# Flipper-ESP32-S2.net
KiCad netlist of a schematic drawn in EAGLE
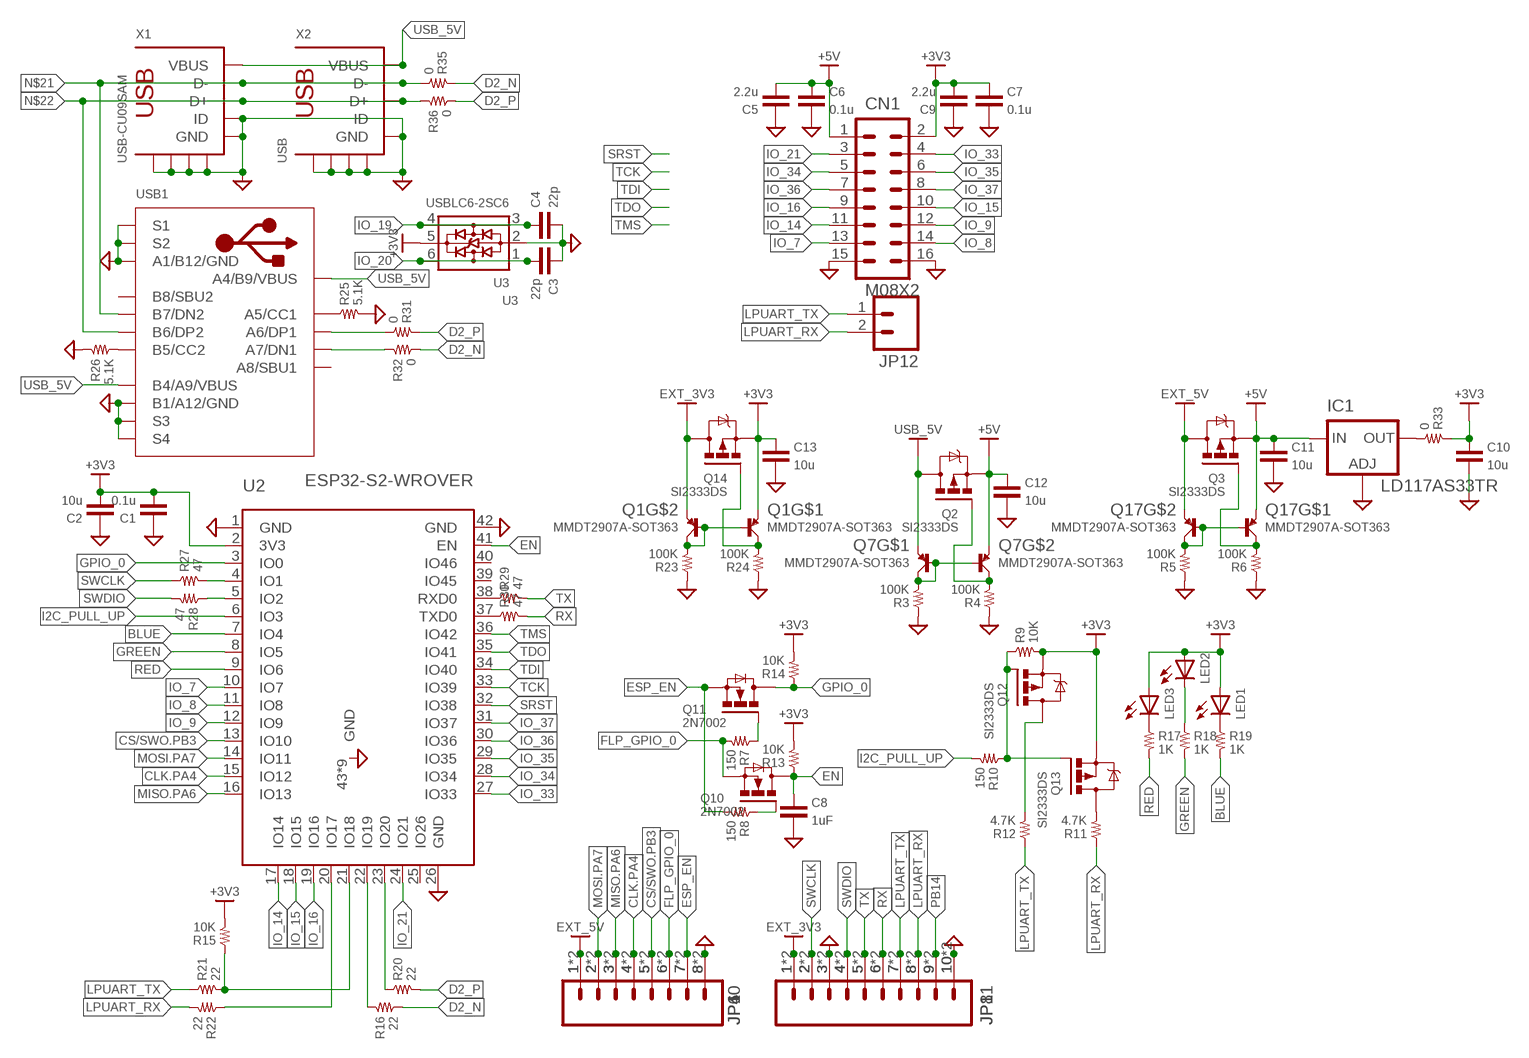
[diagram p0: schematic, sheet 1]

(export (version "E")
  (design (tool "Eeschema 10.0.6"))
  (components
    (comp (ref "C1")
      (value "0.1u")
      (footprint "eagle-import:0603")
      (libsource (lib "eagle-import") (part "CAP-0603"))
    )
    (comp (ref "C2")
      (value "10u")
      (footprint "eagle-import:0805")
      (libsource (lib "eagle-import") (part "CAP-0805"))
    )
    (comp (ref "C3")
      (value "22p")
      (footprint "eagle-import:0603")
      (libsource (lib "eagle-import") (part "CAP-0603"))
    )
    (comp (ref "C4")
      (value "22p")
      (footprint "eagle-import:0603")
      (libsource (lib "eagle-import") (part "CAP-0603"))
    )
    (comp (ref "C5")
      (value "2.2u")
      (footprint "eagle-import:0603")
      (libsource (lib "eagle-import") (part "CAP-0603"))
    )
    (comp (ref "C6")
      (value "0.1u")
      (footprint "eagle-import:0603")
      (libsource (lib "eagle-import") (part "CAP-0603"))
    )
    (comp (ref "C7")
      (value "0.1u")
      (footprint "eagle-import:0603")
      (libsource (lib "eagle-import") (part "CAP-0603"))
    )
    (comp (ref "C8")
      (value "1uF")
      (footprint "eagle-import:0603")
      (libsource (lib "eagle-import") (part "CAP-0603"))
    )
    (comp (ref "C9")
      (value "2.2u")
      (footprint "eagle-import:0603")
      (libsource (lib "eagle-import") (part "CAP-0603"))
    )
    (comp (ref "C10")
      (value "10u")
      (footprint "eagle-import:0805")
      (libsource (lib "eagle-import") (part "CAP-0805"))
    )
    (comp (ref "C11")
      (value "10u")
      (footprint "eagle-import:0805")
      (libsource (lib "eagle-import") (part "CAP-0805"))
    )
    (comp (ref "C12")
      (value "10u")
      (footprint "eagle-import:0805")
      (libsource (lib "eagle-import") (part "CAP-0805"))
    )
    (comp (ref "C13")
      (value "10u")
      (footprint "eagle-import:0805")
      (libsource (lib "eagle-import") (part "CAP-0805"))
    )
    (comp (ref "CN1")
      (value "M08X2")
      (footprint "eagle-import:2X8")
      (libsource (lib "eagle-import") (part "M08X2"))
    )
    (comp (ref "IC1")
      (value "LD117AS33TR")
      (footprint "eagle-import:SOT223")
      (libsource (lib "eagle-import") (part "LD117A?S33TR"))
    )
    (comp (ref "JP1")
      (value "M10\"")
      (footprint "eagle-import:1X10")
      (libsource (lib "eagle-import") (part "M10{dblquote}"))
    )
    (comp (ref "JP4")
      (value "M08SMD-COMBO")
      (footprint "eagle-import:1X08_SMD_COMBINED")
      (libsource (lib "eagle-import") (part "M08SMD-COMBO"))
    )
    (comp (ref "JP6")
      (value "M081X08")
      (footprint "eagle-import:1X08")
      (libsource (lib "eagle-import") (part "M081X08"))
    )
    (comp (ref "JP8")
      (value "M10COMBINED")
      (footprint "eagle-import:1X10_SMD_COMBINED")
      (libsource (lib "eagle-import") (part "M10COMBINED"))
    )
    (comp (ref "JP10")
      (value "M081X08")
      (footprint "eagle-import:1X08")
      (libsource (lib "eagle-import") (part "M081X08"))
    )
    (comp (ref "JP11")
      (value "M10\"")
      (footprint "eagle-import:1X10")
      (libsource (lib "eagle-import") (part "M10{dblquote}"))
    )
    (comp (ref "JP12")
      (value "M02PTH")
      (footprint "eagle-import:1X02")
      (libsource (lib "eagle-import") (part "M02PTH"))
    )
    (comp (ref "LED1")
      (value "LEDCHIPLED_0603")
      (footprint "eagle-import:CHIPLED_0603")
      (libsource (lib "eagle-import") (part "LEDCHIPLED_0603"))
    )
    (comp (ref "LED2")
      (value "LEDCHIPLED_0603")
      (footprint "eagle-import:CHIPLED_0603")
      (libsource (lib "eagle-import") (part "LEDCHIPLED_0603"))
    )
    (comp (ref "LED3")
      (value "LEDCHIPLED_0603")
      (footprint "eagle-import:CHIPLED_0603")
      (libsource (lib "eagle-import") (part "LEDCHIPLED_0603"))
    )
    (comp (ref "Q1")
      (value "MMDT2907A-SOT363")
      (footprint "eagle-import:SOT363")
      (libsource (lib "eagle-import") (part "MMDT2907A-SOT363"))
    )
    (comp (ref "Q2")
      (value "SI2333DS")
      (footprint "eagle-import:SOT-23")
      (libsource (lib "eagle-import") (part "IRLML6401"))
    )
    (comp (ref "Q3")
      (value "SI2333DS")
      (footprint "eagle-import:SOT-23")
      (libsource (lib "eagle-import") (part "IRLML6401"))
    )
    (comp (ref "Q7")
      (value "MMDT2907A-SOT363")
      (footprint "eagle-import:SOT363")
      (libsource (lib "eagle-import") (part "MMDT2907A-SOT363"))
    )
    (comp (ref "Q10")
      (value "2N7002")
      (footprint "eagle-import:SOT-23")
      (libsource (lib "eagle-import") (part "MOSFET-N-SOT23"))
    )
    (comp (ref "Q11")
      (value "2N7002")
      (footprint "eagle-import:SOT-23")
      (libsource (lib "eagle-import") (part "MOSFET-N-SOT23"))
    )
    (comp (ref "Q12")
      (value "SI2333DS")
      (footprint "eagle-import:SOT-23")
      (libsource (lib "eagle-import") (part "IRLML6401"))
    )
    (comp (ref "Q13")
      (value "SI2333DS")
      (footprint "eagle-import:SOT-23")
      (libsource (lib "eagle-import") (part "IRLML6401"))
    )
    (comp (ref "Q14")
      (value "SI2333DS")
      (footprint "eagle-import:SOT-23")
      (libsource (lib "eagle-import") (part "IRLML6401"))
    )
    (comp (ref "Q17")
      (value "MMDT2907A-SOT363")
      (footprint "eagle-import:SOT363")
      (libsource (lib "eagle-import") (part "MMDT2907A-SOT363"))
    )
    (comp (ref "R3")
      (value "100K")
      (footprint "eagle-import:0603")
      (libsource (lib "eagle-import") (part "RESISTOR-0603"))
    )
    (comp (ref "R4")
      (value "100K")
      (footprint "eagle-import:0603")
      (libsource (lib "eagle-import") (part "RESISTOR-0603"))
    )
    (comp (ref "R5")
      (value "100K")
      (footprint "eagle-import:0603")
      (libsource (lib "eagle-import") (part "RESISTOR-0603"))
    )
    (comp (ref "R6")
      (value "100K")
      (footprint "eagle-import:0603")
      (libsource (lib "eagle-import") (part "RESISTOR-0603"))
    )
    (comp (ref "R7")
      (value "150")
      (footprint "eagle-import:0603")
      (libsource (lib "eagle-import") (part "RESISTOR-0603"))
    )
    (comp (ref "R8")
      (value "150")
      (footprint "eagle-import:0603")
      (libsource (lib "eagle-import") (part "RESISTOR-0603"))
    )
    (comp (ref "R9")
      (value "10K")
      (footprint "eagle-import:0603")
      (libsource (lib "eagle-import") (part "RESISTOR-0603"))
    )
    (comp (ref "R10")
      (value "150")
      (footprint "eagle-import:0603")
      (libsource (lib "eagle-import") (part "RESISTOR-0603"))
    )
    (comp (ref "R11")
      (value "4.7K")
      (footprint "eagle-import:0603")
      (libsource (lib "eagle-import") (part "RESISTOR-0603"))
    )
    (comp (ref "R12")
      (value "4.7K")
      (footprint "eagle-import:0603")
      (libsource (lib "eagle-import") (part "RESISTOR-0603"))
    )
    (comp (ref "R13")
      (value "10K")
      (footprint "eagle-import:0603")
      (libsource (lib "eagle-import") (part "RESISTOR-0603"))
    )
    (comp (ref "R14")
      (value "10K")
      (footprint "eagle-import:0603")
      (libsource (lib "eagle-import") (part "RESISTOR-0603"))
    )
    (comp (ref "R15")
      (value "10K")
      (footprint "eagle-import:0603")
      (libsource (lib "eagle-import") (part "RESISTOR-0603"))
    )
    (comp (ref "R16")
      (value "22")
      (footprint "eagle-import:0603")
      (libsource (lib "eagle-import") (part "RESISTOR-0603"))
    )
    (comp (ref "R17")
      (value "1K")
      (footprint "eagle-import:0603")
      (libsource (lib "eagle-import") (part "RESISTOR-0603"))
    )
    (comp (ref "R18")
      (value "1K")
      (footprint "eagle-import:0603")
      (libsource (lib "eagle-import") (part "RESISTOR-0603"))
    )
    (comp (ref "R19")
      (value "1K")
      (footprint "eagle-import:0603")
      (libsource (lib "eagle-import") (part "RESISTOR-0603"))
    )
    (comp (ref "R20")
      (value "22")
      (footprint "eagle-import:0603")
      (libsource (lib "eagle-import") (part "RESISTOR-0603"))
    )
    (comp (ref "R21")
      (value "22")
      (footprint "eagle-import:0603")
      (libsource (lib "eagle-import") (part "RESISTOR-0603"))
    )
    (comp (ref "R22")
      (value "22")
      (footprint "eagle-import:0603")
      (libsource (lib "eagle-import") (part "RESISTOR-0603"))
    )
    (comp (ref "R23")
      (value "100K")
      (footprint "eagle-import:0603")
      (libsource (lib "eagle-import") (part "RESISTOR-0603"))
    )
    (comp (ref "R24")
      (value "100K")
      (footprint "eagle-import:0603")
      (libsource (lib "eagle-import") (part "RESISTOR-0603"))
    )
    (comp (ref "R25")
      (value "5.1K")
      (footprint "eagle-import:0603")
      (libsource (lib "eagle-import") (part "RESISTOR-0603"))
    )
    (comp (ref "R26")
      (value "5.1K")
      (footprint "eagle-import:0603")
      (libsource (lib "eagle-import") (part "RESISTOR-0603"))
    )
    (comp (ref "R27")
      (value "47")
      (footprint "eagle-import:0603")
      (libsource (lib "eagle-import") (part "RESISTOR-0603"))
    )
    (comp (ref "R28")
      (value "47")
      (footprint "eagle-import:0603")
      (libsource (lib "eagle-import") (part "RESISTOR-0603"))
    )
    (comp (ref "R29")
      (value "47")
      (footprint "eagle-import:0603")
      (libsource (lib "eagle-import") (part "RESISTOR-0603"))
    )
    (comp (ref "R30")
      (value "47")
      (footprint "eagle-import:0603")
      (libsource (lib "eagle-import") (part "RESISTOR-0603"))
    )
    (comp (ref "R31")
      (value "0")
      (footprint "eagle-import:0402")
      (libsource (lib "eagle-import") (part "RESISTOR-0402"))
    )
    (comp (ref "R32")
      (value "0")
      (footprint "eagle-import:0402")
      (libsource (lib "eagle-import") (part "RESISTOR-0402"))
    )
    (comp (ref "R33")
      (value "0")
      (footprint "eagle-import:0402")
      (libsource (lib "eagle-import") (part "RESISTOR-0402"))
    )
    (comp (ref "R35")
      (value "0")
      (footprint "eagle-import:0402")
      (libsource (lib "eagle-import") (part "RESISTOR-0402"))
    )
    (comp (ref "R36")
      (value "0")
      (footprint "eagle-import:0402")
      (libsource (lib "eagle-import") (part "RESISTOR-0402"))
    )
    (comp (ref "U2")
      (value "ESP32-S2-WROVER")
      (footprint "eagle-import:ESP32-S2-WROVER")
      (libsource (lib "eagle-import") (part "ESP32-S2-WROVER"))
    )
    (comp (ref "U3")
      (value "USBLC6-2SC6")
      (footprint "eagle-import:SOT23-6")
      (libsource (lib "eagle-import") (part "USBLC6-2SC6"))
    )
    (comp (ref "USB1")
      (value "USB2.0-TYPE-C")
      (footprint "eagle-import:USB2.0-TYPE-C")
      (libsource (lib "eagle-import") (part "USB2.0-TYPE-C"))
    )
    (comp (ref "X1")
      (value "USB-CU09SAM")
      (footprint "eagle-import:CU09SAM")
      (libsource (lib "eagle-import") (part "USB-CU09SAM"))
    )
    (comp (ref "X2")
      (value "USB")
      (footprint "eagle-import:473460001")
      (libsource (lib "eagle-import") (part "USB"))
    )
  )
  (nets
    (net (code "1") (name "+3V3") (class "Default")
      (node (ref "C1") (pin "1") (pinfunction "1_1") (pintype "passive"))
      (node (ref "C10") (pin "2") (pinfunction "2_2") (pintype "passive"))
      (node (ref "C13") (pin "2") (pinfunction "2_2") (pintype "passive"))
      (node (ref "C2") (pin "1") (pinfunction "1_1") (pintype "passive"))
      (node (ref "C7") (pin "2") (pinfunction "2_2") (pintype "passive"))
      (node (ref "C9") (pin "1") (pinfunction "1_1") (pintype "passive"))
      (node (ref "CN1") (pin "2") (pinfunction "2_2") (pintype "passive"))
      (node (ref "LED1") (pin "A") (pinfunction "A_A") (pintype "passive"))
      (node (ref "LED2") (pin "A") (pinfunction "A_A") (pintype "passive"))
      (node (ref "LED3") (pin "A") (pinfunction "A_A") (pintype "passive"))
      (node (ref "Q1") (pin "1") (pinfunction "E_1") (pintype "passive"))
      (node (ref "Q12") (pin "2") (pinfunction "S_2") (pintype "passive"))
      (node (ref "Q13") (pin "2") (pinfunction "S_2") (pintype "passive"))
      (node (ref "Q14") (pin "2") (pinfunction "S_2") (pintype "passive"))
      (node (ref "R13") (pin "2") (pinfunction "2_2") (pintype "passive"))
      (node (ref "R14") (pin "2") (pinfunction "2_2") (pintype "passive"))
      (node (ref "R15") (pin "2") (pinfunction "2_2") (pintype "passive"))
      (node (ref "R33") (pin "1") (pinfunction "1_1") (pintype "passive"))
      (node (ref "R9") (pin "2") (pinfunction "2_2") (pintype "passive"))
      (node (ref "U2") (pin "2") (pinfunction "3V3_2") (pintype "power_in"))
      (node (ref "U3") (pin "5") (pinfunction "VBUS_5") (pintype "passive"))
    )
    (net (code "2") (name "+5V") (class "Default")
      (node (ref "C11") (pin "2") (pinfunction "2_2") (pintype "passive"))
      (node (ref "C12") (pin "2") (pinfunction "2_2") (pintype "passive"))
      (node (ref "C5") (pin "1") (pinfunction "1_1") (pintype "passive"))
      (node (ref "C6") (pin "2") (pinfunction "2_2") (pintype "passive"))
      (node (ref "CN1") (pin "1") (pinfunction "1_1") (pintype "passive"))
      (node (ref "IC1") (pin "3") (pinfunction "IN_3") (pintype "input"))
      (node (ref "Q17") (pin "1") (pinfunction "E_1") (pintype "passive"))
      (node (ref "Q2") (pin "2") (pinfunction "S_2") (pintype "passive"))
      (node (ref "Q3") (pin "2") (pinfunction "S_2") (pintype "passive"))
      (node (ref "Q7") (pin "4") (pinfunction "E_4") (pintype "passive"))
    )
    (net (code "3") (name "BLUE") (class "Default")
      (node (ref "R19") (pin "2") (pinfunction "2_2") (pintype "passive"))
      (node (ref "U2") (pin "7") (pinfunction "IO4_7") (pintype "bidirectional"))
    )
    (net (code "4") (name "CLK.PA4") (class "Default")
      (node (ref "JP10") (pin "4") (pinfunction "4_4") (pintype "passive"))
      (node (ref "JP4") (pin "4") (pinfunction "4_4") (pintype "passive"))
      (node (ref "JP4") (pin "4@2") (pinfunction "4_4@2") (pintype "passive"))
      (node (ref "JP6") (pin "4") (pinfunction "4_4") (pintype "passive"))
      (node (ref "U2") (pin "15") (pinfunction "IO12_15") (pintype "bidirectional"))
    )
    (net (code "5") (name "CS{slash}SWO.PB3") (class "Default")
      (node (ref "JP10") (pin "5") (pinfunction "5_5") (pintype "passive"))
      (node (ref "JP4") (pin "5") (pinfunction "5_5") (pintype "passive"))
      (node (ref "JP4") (pin "5@2") (pinfunction "5_5@2") (pintype "passive"))
      (node (ref "JP6") (pin "5") (pinfunction "5_5") (pintype "passive"))
      (node (ref "U2") (pin "13") (pinfunction "IO10_13") (pintype "bidirectional"))
    )
    (net (code "6") (name "D2_N") (class "Default")
      (node (ref "R16") (pin "2") (pinfunction "2_2") (pintype "passive"))
      (node (ref "R32") (pin "2") (pinfunction "2_2") (pintype "passive"))
      (node (ref "R35") (pin "1") (pinfunction "1_1") (pintype "passive"))
    )
    (net (code "7") (name "D2_P") (class "Default")
      (node (ref "R20") (pin "2") (pinfunction "2_2") (pintype "passive"))
      (node (ref "R31") (pin "1") (pinfunction "1_1") (pintype "passive"))
      (node (ref "R36") (pin "2") (pinfunction "2_2") (pintype "passive"))
    )
    (net (code "8") (name "EN") (class "Default")
      (node (ref "C8") (pin "2") (pinfunction "2_2") (pintype "passive"))
      (node (ref "Q10") (pin "3") (pinfunction "D_3") (pintype "passive"))
      (node (ref "R13") (pin "1") (pinfunction "1_1") (pintype "passive"))
      (node (ref "U2") (pin "41") (pinfunction "EN_41") (pintype "bidirectional"))
    )
    (net (code "9") (name "ESP_EN") (class "Default")
      (node (ref "JP10") (pin "7") (pinfunction "7_7") (pintype "passive"))
      (node (ref "JP4") (pin "7") (pinfunction "7_7") (pintype "passive"))
      (node (ref "JP4") (pin "7@2") (pinfunction "7_7@2") (pintype "passive"))
      (node (ref "JP6") (pin "7") (pinfunction "7_7") (pintype "passive"))
      (node (ref "Q11") (pin "2") (pinfunction "S_2") (pintype "passive"))
      (node (ref "R8") (pin "2") (pinfunction "2_2") (pintype "passive"))
    )
    (net (code "10") (name "EXT_3V3") (class "Default")
      (node (ref "JP1") (pin "1") (pinfunction "1_1") (pintype "passive"))
      (node (ref "JP11") (pin "1") (pinfunction "1_1") (pintype "passive"))
      (node (ref "JP8") (pin "1") (pinfunction "1_1") (pintype "passive"))
      (node (ref "JP8") (pin "1@2") (pinfunction "1_1@2") (pintype "passive"))
      (node (ref "Q1") (pin "4") (pinfunction "E_4") (pintype "passive"))
      (node (ref "Q14") (pin "3") (pinfunction "D_3") (pintype "passive"))
    )
    (net (code "11") (name "EXT_5V") (class "Default")
      (node (ref "JP10") (pin "1") (pinfunction "1_1") (pintype "passive"))
      (node (ref "JP4") (pin "1") (pinfunction "1_1") (pintype "passive"))
      (node (ref "JP4") (pin "1@2") (pinfunction "1_1@2") (pintype "passive"))
      (node (ref "JP6") (pin "1") (pinfunction "1_1") (pintype "passive"))
      (node (ref "Q17") (pin "4") (pinfunction "E_4") (pintype "passive"))
      (node (ref "Q3") (pin "3") (pinfunction "D_3") (pintype "passive"))
    )
    (net (code "12") (name "FLP_GPIO_0") (class "Default")
      (node (ref "JP10") (pin "6") (pinfunction "6_6") (pintype "passive"))
      (node (ref "JP4") (pin "6") (pinfunction "6_6") (pintype "passive"))
      (node (ref "JP4") (pin "6@2") (pinfunction "6_6@2") (pintype "passive"))
      (node (ref "JP6") (pin "6") (pinfunction "6_6") (pintype "passive"))
      (node (ref "Q10") (pin "2") (pinfunction "S_2") (pintype "passive"))
      (node (ref "R7") (pin "2") (pinfunction "2_2") (pintype "passive"))
    )
    (net (code "13") (name "GND") (class "Default")
      (node (ref "C1") (pin "2") (pinfunction "2_2") (pintype "passive"))
      (node (ref "C10") (pin "1") (pinfunction "1_1") (pintype "passive"))
      (node (ref "C11") (pin "1") (pinfunction "1_1") (pintype "passive"))
      (node (ref "C12") (pin "1") (pinfunction "1_1") (pintype "passive"))
      (node (ref "C13") (pin "1") (pinfunction "1_1") (pintype "passive"))
      (node (ref "C2") (pin "2") (pinfunction "2_2") (pintype "passive"))
      (node (ref "C3") (pin "2") (pinfunction "2_2") (pintype "passive"))
      (node (ref "C4") (pin "1") (pinfunction "1_1") (pintype "passive"))
      (node (ref "C5") (pin "2") (pinfunction "2_2") (pintype "passive"))
      (node (ref "C6") (pin "1") (pinfunction "1_1") (pintype "passive"))
      (node (ref "C7") (pin "1") (pinfunction "1_1") (pintype "passive"))
      (node (ref "C8") (pin "1") (pinfunction "1_1") (pintype "passive"))
      (node (ref "C9") (pin "2") (pinfunction "2_2") (pintype "passive"))
      (node (ref "CN1") (pin "15") (pinfunction "15_15") (pintype "passive"))
      (node (ref "CN1") (pin "16") (pinfunction "16_16") (pintype "passive"))
      (node (ref "IC1") (pin "1") (pinfunction "ADJ_1") (pintype "input"))
      (node (ref "JP1") (pin "10") (pinfunction "10_10") (pintype "passive"))
      (node (ref "JP1") (pin "3") (pinfunction "3_3") (pintype "passive"))
      (node (ref "JP10") (pin "8") (pinfunction "8_8") (pintype "passive"))
      (node (ref "JP11") (pin "10") (pinfunction "10_10") (pintype "passive"))
      (node (ref "JP11") (pin "3") (pinfunction "3_3") (pintype "passive"))
      (node (ref "JP4") (pin "8") (pinfunction "8_8") (pintype "passive"))
      (node (ref "JP4") (pin "8@2") (pinfunction "8_8@2") (pintype "passive"))
      (node (ref "JP6") (pin "8") (pinfunction "8_8") (pintype "passive"))
      (node (ref "JP8") (pin "10") (pinfunction "10_10") (pintype "passive"))
      (node (ref "JP8") (pin "10@2") (pinfunction "10_10@2") (pintype "passive"))
      (node (ref "JP8") (pin "3") (pinfunction "3_3") (pintype "passive"))
      (node (ref "JP8") (pin "3@2") (pinfunction "3_3@2") (pintype "passive"))
      (node (ref "R23") (pin "1") (pinfunction "1_1") (pintype "passive"))
      (node (ref "R24") (pin "1") (pinfunction "1_1") (pintype "passive"))
      (node (ref "R25") (pin "2") (pinfunction "2_2") (pintype "passive"))
      (node (ref "R26") (pin "1") (pinfunction "1_1") (pintype "passive"))
      (node (ref "R3") (pin "1") (pinfunction "1_1") (pintype "passive"))
      (node (ref "R4") (pin "1") (pinfunction "1_1") (pintype "passive"))
      (node (ref "R5") (pin "1") (pinfunction "1_1") (pintype "passive"))
      (node (ref "R6") (pin "1") (pinfunction "1_1") (pintype "passive"))
      (node (ref "U2") (pin "1") (pinfunction "GND_1") (pintype "power_in"))
      (node (ref "U2") (pin "26") (pinfunction "GND_26") (pintype "power_in"))
      (node (ref "U2") (pin "42") (pinfunction "GND_42") (pintype "power_in"))
      (node (ref "U2") (pin "43") (pinfunction "GND_43") (pintype "power_in"))
      (node (ref "U2") (pin "44") (pinfunction "GND_44") (pintype "power_in"))
      (node (ref "U2") (pin "45") (pinfunction "GND_45") (pintype "power_in"))
      (node (ref "U2") (pin "46") (pinfunction "GND_46") (pintype "power_in"))
      (node (ref "U2") (pin "47") (pinfunction "GND_47") (pintype "power_in"))
      (node (ref "U2") (pin "48") (pinfunction "GND_48") (pintype "power_in"))
      (node (ref "U2") (pin "49") (pinfunction "GND_49") (pintype "power_in"))
      (node (ref "U2") (pin "50") (pinfunction "GND_50") (pintype "power_in"))
      (node (ref "U2") (pin "51") (pinfunction "GND_51") (pintype "power_in"))
      (node (ref "U3") (pin "2") (pinfunction "GND_2") (pintype "passive"))
      (node (ref "USB1") (pin "A1_B12") (pinfunction "A1/B12/GND_A1_B12") (pintype "passive"))
      (node (ref "USB1") (pin "B1_A12") (pinfunction "B1/A12/GND_B1_A12") (pintype "passive"))
      (node (ref "USB1") (pin "S1") (pinfunction "S1_S1") (pintype "passive"))
      (node (ref "USB1") (pin "S2") (pinfunction "S2_S2") (pintype "passive"))
      (node (ref "USB1") (pin "S3") (pinfunction "S3_S3") (pintype "passive"))
      (node (ref "USB1") (pin "S4") (pinfunction "S4_S4") (pintype "passive"))
      (node (ref "USB1") (pin "S5") (pinfunction "S1_S5") (pintype "passive"))
      (node (ref "USB1") (pin "S6") (pinfunction "S2_S6") (pintype "passive"))
      (node (ref "X1") (pin "4") (pinfunction "ID_4") (pintype "bidirectional"))
      (node (ref "X1") (pin "5") (pinfunction "GND_5") (pintype "power_in"))
      (node (ref "X1") (pin "GND@1") (pinfunction "GND_GND@1") (pintype "power_in"))
      (node (ref "X1") (pin "GND@2") (pinfunction "GND_GND@2") (pintype "power_in"))
      (node (ref "X1") (pin "GND@3") (pinfunction "GND_GND@3") (pintype "power_in"))
      (node (ref "X1") (pin "GND@4") (pinfunction "GND_GND@4") (pintype "power_in"))
      (node (ref "X2") (pin "4") (pinfunction "ID_4") (pintype "bidirectional"))
      (node (ref "X2") (pin "5") (pinfunction "GND_5") (pintype "power_in"))
      (node (ref "X2") (pin "EP@1") (pinfunction "GND_EP@1") (pintype "power_in"))
      (node (ref "X2") (pin "EP@2") (pinfunction "GND_EP@2") (pintype "power_in"))
      (node (ref "X2") (pin "EP@3") (pinfunction "GND_EP@3") (pintype "power_in"))
      (node (ref "X2") (pin "EP@4") (pinfunction "GND_EP@4") (pintype "power_in"))
    )
    (net (code "14") (name "GPIO_0") (class "Default")
      (node (ref "Q11") (pin "3") (pinfunction "D_3") (pintype "passive"))
      (node (ref "R14") (pin "1") (pinfunction "1_1") (pintype "passive"))
      (node (ref "U2") (pin "3") (pinfunction "IO0_3") (pintype "bidirectional"))
    )
    (net (code "15") (name "GREEN") (class "Default")
      (node (ref "R18") (pin "2") (pinfunction "2_2") (pintype "passive"))
      (node (ref "U2") (pin "8") (pinfunction "IO5_8") (pintype "bidirectional"))
    )
    (net (code "16") (name "I2C_PULL_UP") (class "Default")
      (node (ref "R10") (pin "2") (pinfunction "2_2") (pintype "passive"))
      (node (ref "U2") (pin "6") (pinfunction "IO3_6") (pintype "bidirectional"))
    )
    (net (code "17") (name "IO_7") (class "Default")
      (node (ref "CN1") (pin "13") (pinfunction "13_13") (pintype "passive"))
      (node (ref "U2") (pin "10") (pinfunction "IO7_10") (pintype "bidirectional"))
    )
    (net (code "18") (name "IO_8") (class "Default")
      (node (ref "CN1") (pin "14") (pinfunction "14_14") (pintype "passive"))
      (node (ref "U2") (pin "11") (pinfunction "IO8_11") (pintype "bidirectional"))
    )
    (net (code "19") (name "IO_9") (class "Default")
      (node (ref "CN1") (pin "12") (pinfunction "12_12") (pintype "passive"))
      (node (ref "U2") (pin "12") (pinfunction "IO9_12") (pintype "bidirectional"))
    )
    (net (code "20") (name "IO_14") (class "Default")
      (node (ref "CN1") (pin "11") (pinfunction "11_11") (pintype "passive"))
      (node (ref "U2") (pin "17") (pinfunction "IO14_17") (pintype "bidirectional"))
    )
    (net (code "21") (name "IO_15") (class "Default")
      (node (ref "CN1") (pin "10") (pinfunction "10_10") (pintype "passive"))
      (node (ref "U2") (pin "18") (pinfunction "IO15_18") (pintype "bidirectional"))
    )
    (net (code "22") (name "IO_16") (class "Default")
      (node (ref "CN1") (pin "9") (pinfunction "9_9") (pintype "passive"))
      (node (ref "U2") (pin "19") (pinfunction "IO16_19") (pintype "bidirectional"))
    )
    (net (code "23") (name "IO_19") (class "Default")
      (node (ref "C4") (pin "2") (pinfunction "2_2") (pintype "passive"))
      (node (ref "R16") (pin "1") (pinfunction "1_1") (pintype "passive"))
      (node (ref "U2") (pin "22") (pinfunction "IO19_22") (pintype "bidirectional"))
      (node (ref "U3") (pin "3") (pinfunction "IO2_3") (pintype "passive"))
      (node (ref "U3") (pin "4") (pinfunction "IO2_4") (pintype "passive"))
    )
    (net (code "24") (name "IO_20") (class "Default")
      (node (ref "C3") (pin "1") (pinfunction "1_1") (pintype "passive"))
      (node (ref "R20") (pin "1") (pinfunction "1_1") (pintype "passive"))
      (node (ref "U2") (pin "23") (pinfunction "IO20_23") (pintype "bidirectional"))
      (node (ref "U3") (pin "1") (pinfunction "IO1_1") (pintype "passive"))
      (node (ref "U3") (pin "6") (pinfunction "IO1_6") (pintype "passive"))
    )
    (net (code "25") (name "IO_21") (class "Default")
      (node (ref "CN1") (pin "3") (pinfunction "3_3") (pintype "passive"))
      (node (ref "U2") (pin "24") (pinfunction "IO21_24") (pintype "bidirectional"))
    )
    (net (code "26") (name "IO_33") (class "Default")
      (node (ref "CN1") (pin "4") (pinfunction "4_4") (pintype "passive"))
      (node (ref "U2") (pin "27") (pinfunction "IO33_27") (pintype "bidirectional"))
    )
    (net (code "27") (name "IO_34") (class "Default")
      (node (ref "CN1") (pin "5") (pinfunction "5_5") (pintype "passive"))
      (node (ref "U2") (pin "28") (pinfunction "IO34_28") (pintype "bidirectional"))
    )
    (net (code "28") (name "IO_35") (class "Default")
      (node (ref "CN1") (pin "6") (pinfunction "6_6") (pintype "passive"))
      (node (ref "U2") (pin "29") (pinfunction "IO35_29") (pintype "bidirectional"))
    )
    (net (code "29") (name "IO_36") (class "Default")
      (node (ref "CN1") (pin "7") (pinfunction "7_7") (pintype "passive"))
      (node (ref "U2") (pin "30") (pinfunction "IO36_30") (pintype "bidirectional"))
    )
    (net (code "30") (name "IO_37") (class "Default")
      (node (ref "CN1") (pin "8") (pinfunction "8_8") (pintype "passive"))
      (node (ref "U2") (pin "31") (pinfunction "IO37_31") (pintype "bidirectional"))
    )
    (net (code "31") (name "LPUART_RX") (class "Default")
      (node (ref "JP1") (pin "8") (pinfunction "8_8") (pintype "passive"))
      (node (ref "JP11") (pin "8") (pinfunction "8_8") (pintype "passive"))
      (node (ref "JP12") (pin "2") (pinfunction "2_2") (pintype "passive"))
      (node (ref "JP8") (pin "8") (pinfunction "8_8") (pintype "passive"))
      (node (ref "JP8") (pin "8@2") (pinfunction "8_8@2") (pintype "passive"))
      (node (ref "R11") (pin "1") (pinfunction "1_1") (pintype "passive"))
      (node (ref "R22") (pin "2") (pinfunction "2_2") (pintype "passive"))
    )
    (net (code "32") (name "LPUART_TX") (class "Default")
      (node (ref "JP1") (pin "7") (pinfunction "7_7") (pintype "passive"))
      (node (ref "JP11") (pin "7") (pinfunction "7_7") (pintype "passive"))
      (node (ref "JP12") (pin "1") (pinfunction "1_1") (pintype "passive"))
      (node (ref "JP8") (pin "7") (pinfunction "7_7") (pintype "passive"))
      (node (ref "JP8") (pin "7@2") (pinfunction "7_7@2") (pintype "passive"))
      (node (ref "R12") (pin "1") (pinfunction "1_1") (pintype "passive"))
      (node (ref "R21") (pin "1") (pinfunction "1_1") (pintype "passive"))
    )
    (net (code "33") (name "MISO.PA6") (class "Default")
      (node (ref "JP10") (pin "3") (pinfunction "3_3") (pintype "passive"))
      (node (ref "JP4") (pin "3") (pinfunction "3_3") (pintype "passive"))
      (node (ref "JP4") (pin "3@2") (pinfunction "3_3@2") (pintype "passive"))
      (node (ref "JP6") (pin "3") (pinfunction "3_3") (pintype "passive"))
      (node (ref "U2") (pin "16") (pinfunction "IO13_16") (pintype "bidirectional"))
    )
    (net (code "34") (name "MOSI.PA7") (class "Default")
      (node (ref "JP10") (pin "2") (pinfunction "2_2") (pintype "passive"))
      (node (ref "JP4") (pin "2") (pinfunction "2_2") (pintype "passive"))
      (node (ref "JP4") (pin "2@2") (pinfunction "2_2@2") (pintype "passive"))
      (node (ref "JP6") (pin "2") (pinfunction "2_2") (pintype "passive"))
      (node (ref "U2") (pin "14") (pinfunction "IO11_14") (pintype "bidirectional"))
    )
    (net (code "35") (name "N$21") (class "Default")
      (node (ref "R35") (pin "2") (pinfunction "2_2") (pintype "passive"))
      (node (ref "USB1") (pin "B7") (pinfunction "B7/DN2_B7") (pintype "passive"))
      (node (ref "X1") (pin "2") (pinfunction "D-_2") (pintype "bidirectional"))
      (node (ref "X2") (pin "2") (pinfunction "D-_2") (pintype "bidirectional"))
    )
    (net (code "36") (name "N$22") (class "Default")
      (node (ref "R36") (pin "1") (pinfunction "1_1") (pintype "passive"))
      (node (ref "USB1") (pin "B6") (pinfunction "B6/DP2_B6") (pintype "passive"))
      (node (ref "X1") (pin "3") (pinfunction "D+_3") (pintype "bidirectional"))
      (node (ref "X2") (pin "3") (pinfunction "D+_3") (pintype "bidirectional"))
    )
    (net (code "37") (name "Net-(IC1-OUT-Pad2)") (class "Default")
      (node (ref "IC1") (pin "2") (pinfunction "OUT_2") (pintype "passive"))
      (node (ref "IC1") (pin "4") (pinfunction "OUT_4") (pintype "passive"))
      (node (ref "R33") (pin "2") (pinfunction "2_2") (pintype "passive"))
    )
    (net (code "38") (name "Net-(LED1-PadC)") (class "Default")
      (node (ref "LED1") (pin "C") (pinfunction "C_C") (pintype "passive"))
      (node (ref "R19") (pin "1") (pinfunction "1_1") (pintype "passive"))
    )
    (net (code "39") (name "Net-(LED2-PadC)") (class "Default")
      (node (ref "LED2") (pin "C") (pinfunction "C_C") (pintype "passive"))
      (node (ref "R18") (pin "1") (pinfunction "1_1") (pintype "passive"))
    )
    (net (code "40") (name "Net-(LED3-PadC)") (class "Default")
      (node (ref "LED3") (pin "C") (pinfunction "C_C") (pintype "passive"))
      (node (ref "R17") (pin "1") (pinfunction "1_1") (pintype "passive"))
    )
    (net (code "41") (name "Net-(Q1A-B)") (class "Default")
      (node (ref "Q1") (pin "2") (pinfunction "B_2") (pintype "passive"))
      (node (ref "Q1") (pin "3") (pinfunction "C_3") (pintype "passive"))
      (node (ref "Q1") (pin "5") (pinfunction "B_5") (pintype "passive"))
      (node (ref "R23") (pin "2") (pinfunction "2_2") (pintype "passive"))
    )
    (net (code "42") (name "Net-(Q2-G)") (class "Default")
      (node (ref "Q2") (pin "1") (pinfunction "G_1") (pintype "passive"))
      (node (ref "Q7") (pin "3") (pinfunction "C_3") (pintype "passive"))
      (node (ref "R4") (pin "2") (pinfunction "2_2") (pintype "passive"))
    )
    (net (code "43") (name "Net-(Q7A-B)") (class "Default")
      (node (ref "Q7") (pin "2") (pinfunction "B_2") (pintype "passive"))
      (node (ref "Q7") (pin "5") (pinfunction "B_5") (pintype "passive"))
      (node (ref "Q7") (pin "6") (pinfunction "C_6") (pintype "passive"))
      (node (ref "R3") (pin "2") (pinfunction "2_2") (pintype "passive"))
    )
    (net (code "44") (name "Net-(Q10-G)") (class "Default")
      (node (ref "Q10") (pin "1") (pinfunction "G_1") (pintype "passive"))
      (node (ref "R8") (pin "1") (pinfunction "1_1") (pintype "passive"))
    )
    (net (code "45") (name "Net-(Q11-G)") (class "Default")
      (node (ref "Q11") (pin "1") (pinfunction "G_1") (pintype "passive"))
      (node (ref "R7") (pin "1") (pinfunction "1_1") (pintype "passive"))
    )
    (net (code "46") (name "Net-(Q12-D)") (class "Default")
      (node (ref "Q12") (pin "3") (pinfunction "D_3") (pintype "passive"))
      (node (ref "R12") (pin "2") (pinfunction "2_2") (pintype "passive"))
    )
    (net (code "47") (name "Net-(Q12-G)") (class "Default")
      (node (ref "Q12") (pin "1") (pinfunction "G_1") (pintype "passive"))
      (node (ref "Q13") (pin "1") (pinfunction "G_1") (pintype "passive"))
      (node (ref "R10") (pin "1") (pinfunction "1_1") (pintype "passive"))
      (node (ref "R9") (pin "1") (pinfunction "1_1") (pintype "passive"))
    )
    (net (code "48") (name "Net-(Q13-D)") (class "Default")
      (node (ref "Q13") (pin "3") (pinfunction "D_3") (pintype "passive"))
      (node (ref "R11") (pin "2") (pinfunction "2_2") (pintype "passive"))
    )
    (net (code "49") (name "Net-(Q14-G)") (class "Default")
      (node (ref "Q1") (pin "6") (pinfunction "C_6") (pintype "passive"))
      (node (ref "Q14") (pin "1") (pinfunction "G_1") (pintype "passive"))
      (node (ref "R24") (pin "2") (pinfunction "2_2") (pintype "passive"))
    )
    (net (code "50") (name "Net-(Q17A-B)") (class "Default")
      (node (ref "Q17") (pin "2") (pinfunction "B_2") (pintype "passive"))
      (node (ref "Q17") (pin "3") (pinfunction "C_3") (pintype "passive"))
      (node (ref "Q17") (pin "5") (pinfunction "B_5") (pintype "passive"))
      (node (ref "R5") (pin "2") (pinfunction "2_2") (pintype "passive"))
    )
    (net (code "51") (name "Net-(Q17A-C)") (class "Default")
      (node (ref "Q17") (pin "6") (pinfunction "C_6") (pintype "passive"))
      (node (ref "Q3") (pin "1") (pinfunction "G_1") (pintype "passive"))
      (node (ref "R6") (pin "2") (pinfunction "2_2") (pintype "passive"))
    )
    (net (code "52") (name "Net-(U2-IO1)") (class "Default")
      (node (ref "R27") (pin "2") (pinfunction "2_2") (pintype "passive"))
      (node (ref "U2") (pin "4") (pinfunction "IO1_4") (pintype "bidirectional"))
    )
    (net (code "53") (name "Net-(U2-IO2)") (class "Default")
      (node (ref "R28") (pin "1") (pinfunction "1_1") (pintype "passive"))
      (node (ref "U2") (pin "5") (pinfunction "IO2_5") (pintype "bidirectional"))
    )
    (net (code "54") (name "Net-(U2-IO17)") (class "Default")
      (node (ref "R22") (pin "1") (pinfunction "1_1") (pintype "passive"))
      (node (ref "U2") (pin "20") (pinfunction "IO17_20") (pintype "bidirectional"))
    )
    (net (code "55") (name "Net-(U2-IO18)") (class "Default")
      (node (ref "R15") (pin "1") (pinfunction "1_1") (pintype "passive"))
      (node (ref "R21") (pin "2") (pinfunction "2_2") (pintype "passive"))
      (node (ref "U2") (pin "21") (pinfunction "IO18_21") (pintype "bidirectional"))
    )
    (net (code "56") (name "Net-(U2-RXD0)") (class "Default")
      (node (ref "R29") (pin "1") (pinfunction "1_1") (pintype "passive"))
      (node (ref "U2") (pin "38") (pinfunction "RXD0_38") (pintype "bidirectional"))
    )
    (net (code "57") (name "Net-(U2-TXD0)") (class "Default")
      (node (ref "R30") (pin "1") (pinfunction "1_1") (pintype "passive"))
      (node (ref "U2") (pin "37") (pinfunction "TXD0_37") (pintype "bidirectional"))
    )
    (net (code "58") (name "Net-(USB1-A5{slash}CC1)") (class "Default")
      (node (ref "R25") (pin "1") (pinfunction "1_1") (pintype "passive"))
      (node (ref "USB1") (pin "A5") (pinfunction "A5/CC1_A5") (pintype "passive"))
    )
    (net (code "59") (name "Net-(USB1-A6{slash}DP1)") (class "Default")
      (node (ref "R31") (pin "2") (pinfunction "2_2") (pintype "passive"))
      (node (ref "USB1") (pin "A6") (pinfunction "A6/DP1_A6") (pintype "passive"))
    )
    (net (code "60") (name "Net-(USB1-A7{slash}DN1)") (class "Default")
      (node (ref "R32") (pin "1") (pinfunction "1_1") (pintype "passive"))
      (node (ref "USB1") (pin "A7") (pinfunction "A7/DN1_A7") (pintype "passive"))
    )
    (net (code "61") (name "Net-(USB1-B5{slash}CC2)") (class "Default")
      (node (ref "R26") (pin "2") (pinfunction "2_2") (pintype "passive"))
      (node (ref "USB1") (pin "B5") (pinfunction "B5/CC2_B5") (pintype "passive"))
    )
    (net (code "62") (name "PB14") (class "Default")
      (node (ref "JP1") (pin "9") (pinfunction "9_9") (pintype "passive"))
      (node (ref "JP11") (pin "9") (pinfunction "9_9") (pintype "passive"))
      (node (ref "JP8") (pin "9") (pinfunction "9_9") (pintype "passive"))
      (node (ref "JP8") (pin "9@2") (pinfunction "9_9@2") (pintype "passive"))
    )
    (net (code "63") (name "RED") (class "Default")
      (node (ref "R17") (pin "2") (pinfunction "2_2") (pintype "passive"))
      (node (ref "U2") (pin "9") (pinfunction "IO6_9") (pintype "bidirectional"))
    )
    (net (code "64") (name "RX") (class "Default")
      (node (ref "JP1") (pin "6") (pinfunction "6_6") (pintype "passive"))
      (node (ref "JP11") (pin "6") (pinfunction "6_6") (pintype "passive"))
      (node (ref "JP8") (pin "6") (pinfunction "6_6") (pintype "passive"))
      (node (ref "JP8") (pin "6@2") (pinfunction "6_6@2") (pintype "passive"))
      (node (ref "R30") (pin "2") (pinfunction "2_2") (pintype "passive"))
    )
    (net (code "65") (name "SRST") (class "Default")
      (node (ref "U2") (pin "32") (pinfunction "IO38_32") (pintype "bidirectional"))
    )
    (net (code "66") (name "SWCLK") (class "Default")
      (node (ref "JP1") (pin "2") (pinfunction "2_2") (pintype "passive"))
      (node (ref "JP11") (pin "2") (pinfunction "2_2") (pintype "passive"))
      (node (ref "JP8") (pin "2") (pinfunction "2_2") (pintype "passive"))
      (node (ref "JP8") (pin "2@2") (pinfunction "2_2@2") (pintype "passive"))
      (node (ref "R27") (pin "1") (pinfunction "1_1") (pintype "passive"))
    )
    (net (code "67") (name "SWDIO") (class "Default")
      (node (ref "JP1") (pin "4") (pinfunction "4_4") (pintype "passive"))
      (node (ref "JP11") (pin "4") (pinfunction "4_4") (pintype "passive"))
      (node (ref "JP8") (pin "4") (pinfunction "4_4") (pintype "passive"))
      (node (ref "JP8") (pin "4@2") (pinfunction "4_4@2") (pintype "passive"))
      (node (ref "R28") (pin "2") (pinfunction "2_2") (pintype "passive"))
    )
    (net (code "68") (name "TCK") (class "Default")
      (node (ref "U2") (pin "33") (pinfunction "IO39_33") (pintype "bidirectional"))
    )
    (net (code "69") (name "TDI") (class "Default")
      (node (ref "U2") (pin "34") (pinfunction "IO40_34") (pintype "bidirectional"))
    )
    (net (code "70") (name "TDO") (class "Default")
      (node (ref "U2") (pin "35") (pinfunction "IO41_35") (pintype "bidirectional"))
    )
    (net (code "71") (name "TMS") (class "Default")
      (node (ref "U2") (pin "36") (pinfunction "IO42_36") (pintype "bidirectional"))
    )
    (net (code "72") (name "TX") (class "Default")
      (node (ref "JP1") (pin "5") (pinfunction "5_5") (pintype "passive"))
      (node (ref "JP11") (pin "5") (pinfunction "5_5") (pintype "passive"))
      (node (ref "JP8") (pin "5") (pinfunction "5_5") (pintype "passive"))
      (node (ref "JP8") (pin "5@2") (pinfunction "5_5@2") (pintype "passive"))
      (node (ref "R29") (pin "2") (pinfunction "2_2") (pintype "passive"))
    )
    (net (code "73") (name "USB_5V") (class "Default")
      (node (ref "Q2") (pin "3") (pinfunction "D_3") (pintype "passive"))
      (node (ref "Q7") (pin "1") (pinfunction "E_1") (pintype "passive"))
      (node (ref "USB1") (pin "A4_B9") (pinfunction "A4/B9/VBUS_A4_B9") (pintype "passive"))
      (node (ref "USB1") (pin "B4_A9") (pinfunction "B4/A9/VBUS_B4_A9") (pintype "passive"))
      (node (ref "X1") (pin "1") (pinfunction "VBUS_1") (pintype "passive"))
      (node (ref "X2") (pin "1") (pinfunction "VBUS_1") (pintype "passive"))
    )
    (net (code "74") (name "unconnected-(U2-IO26-Pad25)") (class "Default")
      (node (ref "U2") (pin "25") (pinfunction "IO26_25") (pintype "bidirectional"))
    )
    (net (code "75") (name "unconnected-(U2-IO45-Pad39)") (class "Default")
      (node (ref "U2") (pin "39") (pinfunction "IO45_39") (pintype "bidirectional"))
    )
    (net (code "76") (name "unconnected-(U2-IO46-Pad40)") (class "Default")
      (node (ref "U2") (pin "40") (pinfunction "IO46_40") (pintype "bidirectional"))
    )
    (net (code "77") (name "unconnected-(USB1-A8{slash}SBU1-PadA8)") (class "Default")
      (node (ref "USB1") (pin "A8") (pinfunction "A8/SBU1_A8") (pintype "passive"))
    )
    (net (code "78") (name "unconnected-(USB1-B8{slash}SBU2-PadB8)") (class "Default")
      (node (ref "USB1") (pin "B8") (pinfunction "B8/SBU2_B8") (pintype "passive"))
    )
  )
)
